# piezopiano.net
KiCad netlist of a schematic drawn in EAGLE
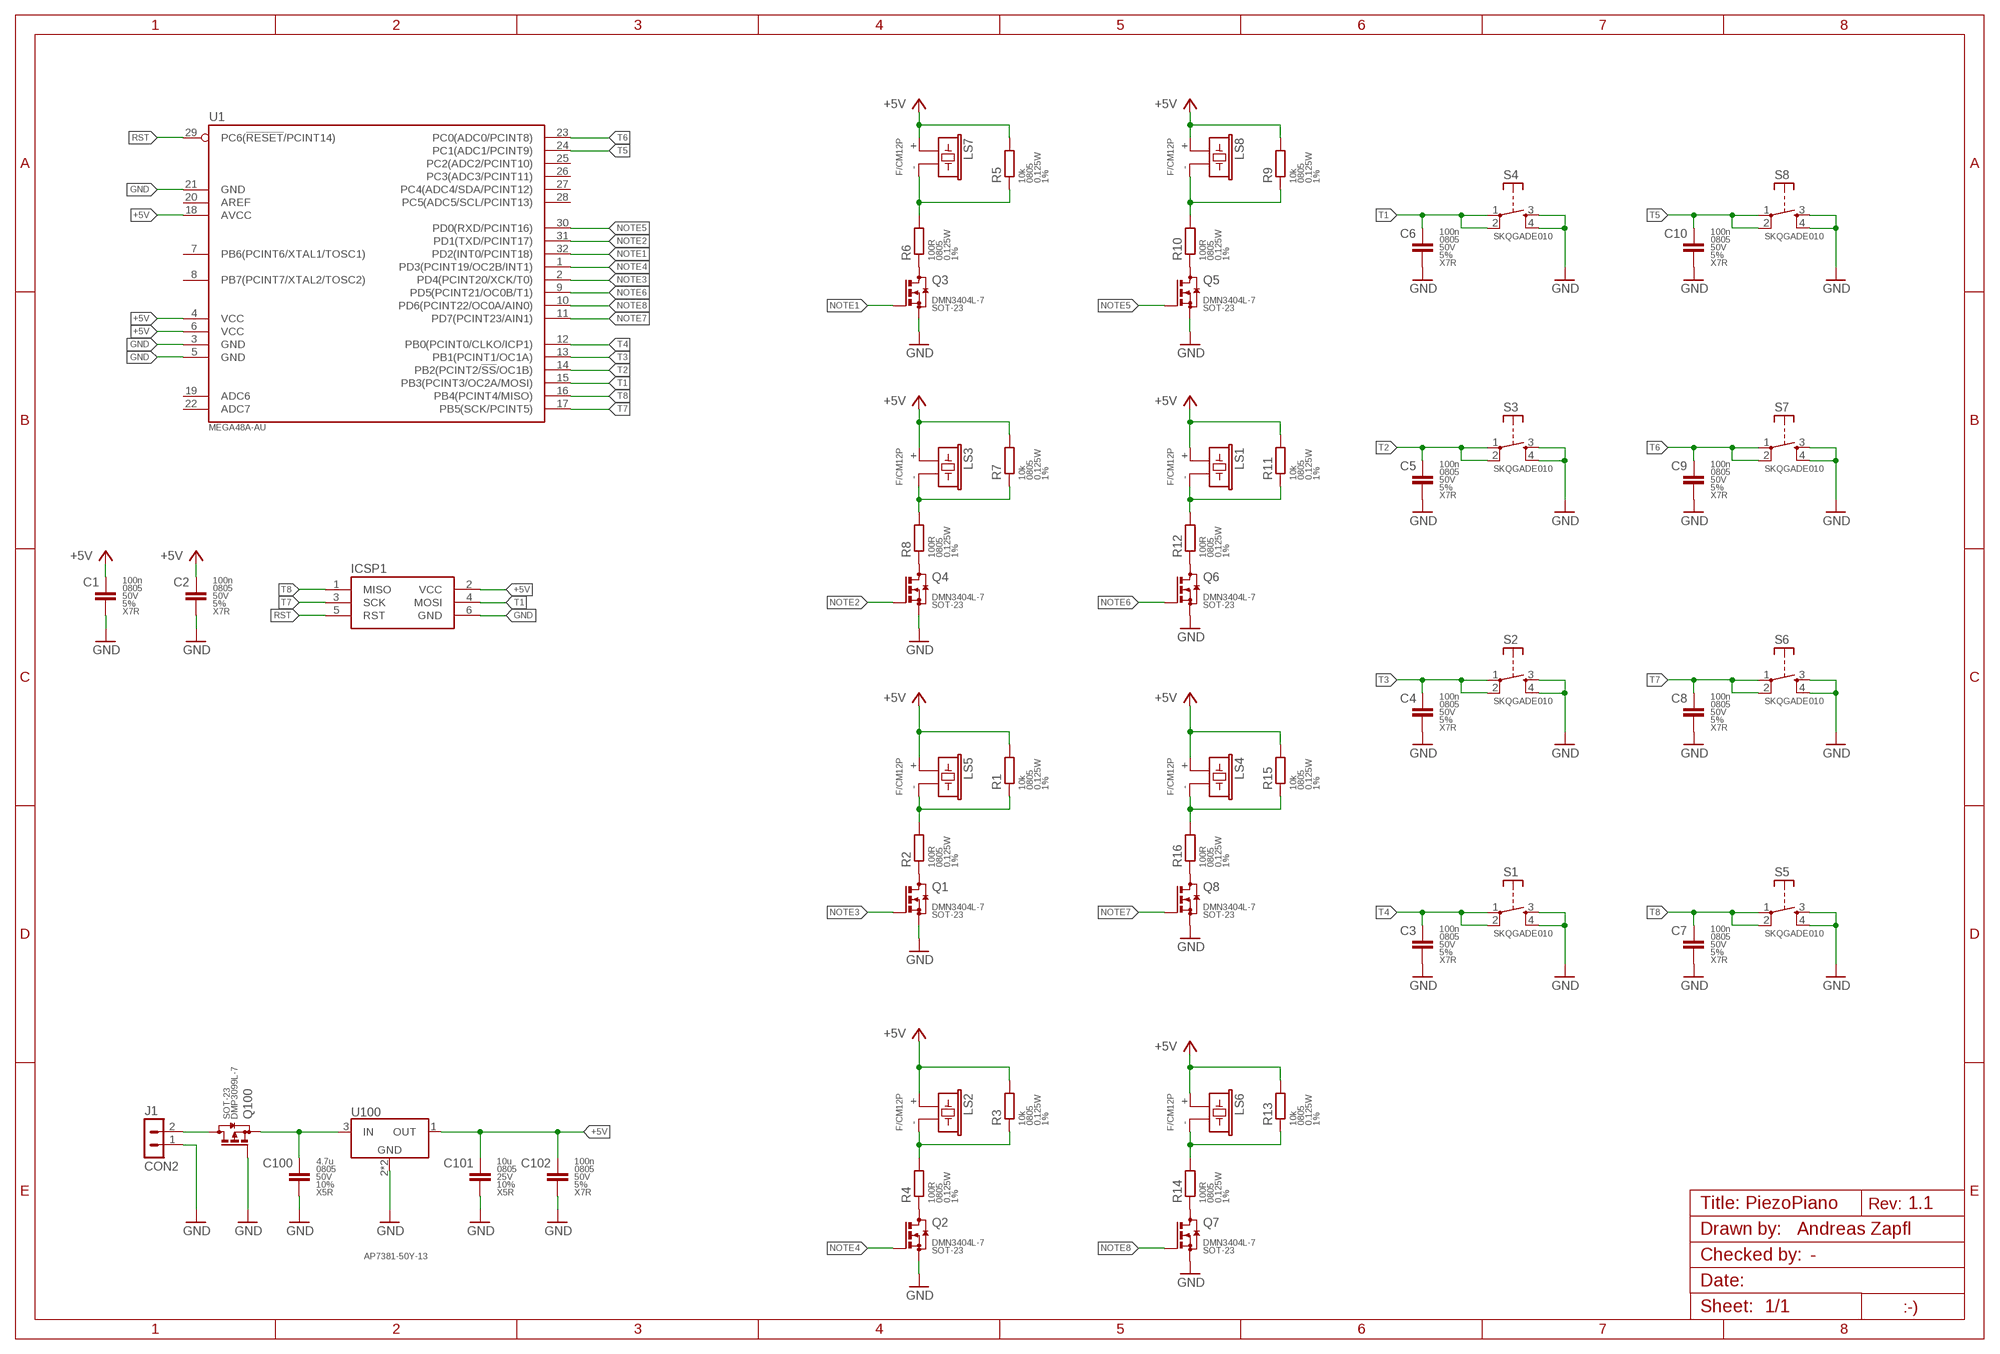
[diagram p0: schematic, sheet 1]

(export (version "E")
  (design (tool "Eeschema 10.0.6"))
  (components
    (comp (ref "C1")
      (value "100n")
      (footprint "eagle-import:C0805")
      (fields
        (field (name "PACKAGE-IN") "0805")
        (field (name "VOLTAGE") "50V")
        (field (name "TOLERANCE") "5%")
        (field (name "DIELECTRIC") "X7R")
        (field (name "MF") "Yageo")
        (field (name "MPN") "CC0805JRX7R9BB104")
      )
      (libsource (lib "eagle-import") (part "100NF-0805-50V-5%"))
    )
    (comp (ref "C2")
      (value "100n")
      (footprint "eagle-import:C0805")
      (fields
        (field (name "PACKAGE-IN") "0805")
        (field (name "VOLTAGE") "50V")
        (field (name "TOLERANCE") "5%")
        (field (name "DIELECTRIC") "X7R")
        (field (name "MF") "Yageo")
        (field (name "MPN") "CC0805JRX7R9BB104")
      )
      (libsource (lib "eagle-import") (part "100NF-0805-50V-5%"))
    )
    (comp (ref "C3")
      (value "100n")
      (footprint "eagle-import:C0805")
      (fields
        (field (name "PACKAGE-IN") "0805")
        (field (name "VOLTAGE") "50V")
        (field (name "TOLERANCE") "5%")
        (field (name "DIELECTRIC") "X7R")
        (field (name "MF") "Yageo")
        (field (name "MPN") "CC0805JRX7R9BB104")
      )
      (libsource (lib "eagle-import") (part "100NF-0805-50V-5%"))
    )
    (comp (ref "C4")
      (value "100n")
      (footprint "eagle-import:C0805")
      (fields
        (field (name "PACKAGE-IN") "0805")
        (field (name "VOLTAGE") "50V")
        (field (name "TOLERANCE") "5%")
        (field (name "DIELECTRIC") "X7R")
        (field (name "MF") "Yageo")
        (field (name "MPN") "CC0805JRX7R9BB104")
      )
      (libsource (lib "eagle-import") (part "100NF-0805-50V-5%"))
    )
    (comp (ref "C5")
      (value "100n")
      (footprint "eagle-import:C0805")
      (fields
        (field (name "PACKAGE-IN") "0805")
        (field (name "VOLTAGE") "50V")
        (field (name "TOLERANCE") "5%")
        (field (name "DIELECTRIC") "X7R")
        (field (name "MF") "Yageo")
        (field (name "MPN") "CC0805JRX7R9BB104")
      )
      (libsource (lib "eagle-import") (part "100NF-0805-50V-5%"))
    )
    (comp (ref "C6")
      (value "100n")
      (footprint "eagle-import:C0805")
      (fields
        (field (name "PACKAGE-IN") "0805")
        (field (name "VOLTAGE") "50V")
        (field (name "TOLERANCE") "5%")
        (field (name "DIELECTRIC") "X7R")
        (field (name "MF") "Yageo")
        (field (name "MPN") "CC0805JRX7R9BB104")
      )
      (libsource (lib "eagle-import") (part "100NF-0805-50V-5%"))
    )
    (comp (ref "C7")
      (value "100n")
      (footprint "eagle-import:C0805")
      (fields
        (field (name "PACKAGE-IN") "0805")
        (field (name "VOLTAGE") "50V")
        (field (name "TOLERANCE") "5%")
        (field (name "DIELECTRIC") "X7R")
        (field (name "MF") "Yageo")
        (field (name "MPN") "CC0805JRX7R9BB104")
      )
      (libsource (lib "eagle-import") (part "100NF-0805-50V-5%"))
    )
    (comp (ref "C8")
      (value "100n")
      (footprint "eagle-import:C0805")
      (fields
        (field (name "PACKAGE-IN") "0805")
        (field (name "VOLTAGE") "50V")
        (field (name "TOLERANCE") "5%")
        (field (name "DIELECTRIC") "X7R")
        (field (name "MF") "Yageo")
        (field (name "MPN") "CC0805JRX7R9BB104")
      )
      (libsource (lib "eagle-import") (part "100NF-0805-50V-5%"))
    )
    (comp (ref "C9")
      (value "100n")
      (footprint "eagle-import:C0805")
      (fields
        (field (name "PACKAGE-IN") "0805")
        (field (name "VOLTAGE") "50V")
        (field (name "TOLERANCE") "5%")
        (field (name "DIELECTRIC") "X7R")
        (field (name "MF") "Yageo")
        (field (name "MPN") "CC0805JRX7R9BB104")
      )
      (libsource (lib "eagle-import") (part "100NF-0805-50V-5%"))
    )
    (comp (ref "C10")
      (value "100n")
      (footprint "eagle-import:C0805")
      (fields
        (field (name "PACKAGE-IN") "0805")
        (field (name "VOLTAGE") "50V")
        (field (name "TOLERANCE") "5%")
        (field (name "DIELECTRIC") "X7R")
        (field (name "MF") "Yageo")
        (field (name "MPN") "CC0805JRX7R9BB104")
      )
      (libsource (lib "eagle-import") (part "100NF-0805-50V-5%"))
    )
    (comp (ref "C100")
      (value "4.7u")
      (footprint "eagle-import:C0805")
      (fields
        (field (name "PACKAGE-IN") "0805")
        (field (name "VOLTAGE") "50V")
        (field (name "TOLERANCE") "10%")
        (field (name "DIELECTRIC") "X5R")
        (field (name "MF") "Murata")
        (field (name "MPN") "GRM21BR61H475KE51L")
      )
      (libsource (lib "eagle-import") (part "4.7UF-0805-50V-10%"))
    )
    (comp (ref "C101")
      (value "10u")
      (footprint "eagle-import:C0805")
      (fields
        (field (name "PACKAGE-IN") "0805")
        (field (name "VOLTAGE") "25V")
        (field (name "TOLERANCE") "10%")
        (field (name "DIELECTRIC") "X5R")
        (field (name "MF") "Murata")
        (field (name "MPN") "GRJ21BR61E106KE01K")
      )
      (libsource (lib "eagle-import") (part "10UF-0805-25V-10%"))
    )
    (comp (ref "C102")
      (value "100n")
      (footprint "eagle-import:C0805")
      (fields
        (field (name "PACKAGE-IN") "0805")
        (field (name "VOLTAGE") "50V")
        (field (name "TOLERANCE") "5%")
        (field (name "DIELECTRIC") "X7R")
        (field (name "MF") "Yageo")
        (field (name "MPN") "CC0805JRX7R9BB104")
      )
      (libsource (lib "eagle-import") (part "100NF-0805-50V-5%"))
    )
    (comp (ref "ICSP1")
      (value "AVRISP2.54MM")
      (footprint "eagle-import:AVRISP-2.54")
      (libsource (lib "eagle-import") (part "AVRISP2.54MM"))
    )
    (comp (ref "J1")
      (value "CON2")
      (footprint "eagle-import:H2-2.54")
      (libsource (lib "eagle-import") (part "CON2"))
    )
    (comp (ref "LS1")
      (value "F/CM12P")
      (footprint "eagle-import:CM12P_5.0P")
      (fields (field (name "MF") "ZLFY") (field (name "MPN") "ZL-YDW1207-4005PA-5.0"))
      (libsource (lib "eagle-import") (part "F/CM12P"))
    )
    (comp (ref "LS2")
      (value "F/CM12P")
      (footprint "eagle-import:CM12P_5.0P")
      (fields (field (name "MF") "ZLFY") (field (name "MPN") "ZL-YDW1207-4005PA-5.0"))
      (libsource (lib "eagle-import") (part "F/CM12P"))
    )
    (comp (ref "LS3")
      (value "F/CM12P")
      (footprint "eagle-import:CM12P_5.0P")
      (fields (field (name "MF") "ZLFY") (field (name "MPN") "ZL-YDW1207-4005PA-5.0"))
      (libsource (lib "eagle-import") (part "F/CM12P"))
    )
    (comp (ref "LS4")
      (value "F/CM12P")
      (footprint "eagle-import:CM12P_5.0P")
      (fields (field (name "MF") "ZLFY") (field (name "MPN") "ZL-YDW1207-4005PA-5.0"))
      (libsource (lib "eagle-import") (part "F/CM12P"))
    )
    (comp (ref "LS5")
      (value "F/CM12P")
      (footprint "eagle-import:CM12P_5.0P")
      (fields (field (name "MF") "ZLFY") (field (name "MPN") "ZL-YDW1207-4005PA-5.0"))
      (libsource (lib "eagle-import") (part "F/CM12P"))
    )
    (comp (ref "LS6")
      (value "F/CM12P")
      (footprint "eagle-import:CM12P_5.0P")
      (fields (field (name "MF") "ZLFY") (field (name "MPN") "ZL-YDW1207-4005PA-5.0"))
      (libsource (lib "eagle-import") (part "F/CM12P"))
    )
    (comp (ref "LS7")
      (value "F/CM12P")
      (footprint "eagle-import:CM12P_5.0P")
      (fields (field (name "MF") "ZLFY") (field (name "MPN") "ZL-YDW1207-4005PA-5.0"))
      (libsource (lib "eagle-import") (part "F/CM12P"))
    )
    (comp (ref "LS8")
      (value "F/CM12P")
      (footprint "eagle-import:CM12P_5.0P")
      (fields (field (name "MF") "ZLFY") (field (name "MPN") "ZL-YDW1207-4005PA-5.0"))
      (libsource (lib "eagle-import") (part "F/CM12P"))
    )
    (comp (ref "Q1")
      (value "DMN3404L")
      (footprint "eagle-import:SOT23")
      (fields
        (field (name "MPN") "DMN3404L-7")
        (field (name "PACKAGE") "SOT-23")
        (field (name "MF") "Diodes Incorporated")
      )
      (libsource (lib "eagle-import") (part "DMN3404L"))
    )
    (comp (ref "Q2")
      (value "DMN3404L")
      (footprint "eagle-import:SOT23")
      (fields
        (field (name "MPN") "DMN3404L-7")
        (field (name "PACKAGE") "SOT-23")
        (field (name "MF") "Diodes Incorporated")
      )
      (libsource (lib "eagle-import") (part "DMN3404L"))
    )
    (comp (ref "Q3")
      (value "DMN3404L")
      (footprint "eagle-import:SOT23")
      (fields
        (field (name "MPN") "DMN3404L-7")
        (field (name "PACKAGE") "SOT-23")
        (field (name "MF") "Diodes Incorporated")
      )
      (libsource (lib "eagle-import") (part "DMN3404L"))
    )
    (comp (ref "Q4")
      (value "DMN3404L")
      (footprint "eagle-import:SOT23")
      (fields
        (field (name "MPN") "DMN3404L-7")
        (field (name "PACKAGE") "SOT-23")
        (field (name "MF") "Diodes Incorporated")
      )
      (libsource (lib "eagle-import") (part "DMN3404L"))
    )
    (comp (ref "Q5")
      (value "DMN3404L")
      (footprint "eagle-import:SOT23")
      (fields
        (field (name "MPN") "DMN3404L-7")
        (field (name "PACKAGE") "SOT-23")
        (field (name "MF") "Diodes Incorporated")
      )
      (libsource (lib "eagle-import") (part "DMN3404L"))
    )
    (comp (ref "Q6")
      (value "DMN3404L")
      (footprint "eagle-import:SOT23")
      (fields
        (field (name "MPN") "DMN3404L-7")
        (field (name "PACKAGE") "SOT-23")
        (field (name "MF") "Diodes Incorporated")
      )
      (libsource (lib "eagle-import") (part "DMN3404L"))
    )
    (comp (ref "Q7")
      (value "DMN3404L")
      (footprint "eagle-import:SOT23")
      (fields
        (field (name "MPN") "DMN3404L-7")
        (field (name "PACKAGE") "SOT-23")
        (field (name "MF") "Diodes Incorporated")
      )
      (libsource (lib "eagle-import") (part "DMN3404L"))
    )
    (comp (ref "Q8")
      (value "DMN3404L")
      (footprint "eagle-import:SOT23")
      (fields
        (field (name "MPN") "DMN3404L-7")
        (field (name "PACKAGE") "SOT-23")
        (field (name "MF") "Diodes Incorporated")
      )
      (libsource (lib "eagle-import") (part "DMN3404L"))
    )
    (comp (ref "Q100")
      (value "DMP3099L")
      (footprint "eagle-import:SOT23")
      (fields
        (field (name "MPN") "DMP3099L-7")
        (field (name "PACKAGE") "SOT-23")
        (field (name "MF") "Diodes Incorporated")
      )
      (libsource (lib "eagle-import") (part "DMP3099L"))
    )
    (comp (ref "R1")
      (value "10k")
      (footprint "eagle-import:R0805")
      (fields
        (field (name "PACKAGE-IN") "0805")
        (field (name "POWER") "0.125W")
        (field (name "TOLERANCE") "1%")
        (field (name "MF") "Yageo")
        (field (name "MPN") "RC0805FR-0710KL")
        (field (name "VOLTAGE") "150V")
      )
      (libsource (lib "eagle-import") (part "10KOHM-0805-1/8W-1%"))
    )
    (comp (ref "R2")
      (value "100R")
      (footprint "eagle-import:R0805")
      (fields
        (field (name "PACKAGE-IN") "0805")
        (field (name "POWER") "0.125W")
        (field (name "TOLERANCE") "1%")
        (field (name "MF") "Yageo")
        (field (name "MPN") "RC0805FR-07100RL")
        (field (name "VOLTAGE") "150V")
      )
      (libsource (lib "eagle-import") (part "100OHM-0805-1/8W-1%"))
    )
    (comp (ref "R3")
      (value "10k")
      (footprint "eagle-import:R0805")
      (fields
        (field (name "PACKAGE-IN") "0805")
        (field (name "POWER") "0.125W")
        (field (name "TOLERANCE") "1%")
        (field (name "MF") "Yageo")
        (field (name "MPN") "RC0805FR-0710KL")
        (field (name "VOLTAGE") "150V")
      )
      (libsource (lib "eagle-import") (part "10KOHM-0805-1/8W-1%"))
    )
    (comp (ref "R4")
      (value "100R")
      (footprint "eagle-import:R0805")
      (fields
        (field (name "PACKAGE-IN") "0805")
        (field (name "POWER") "0.125W")
        (field (name "TOLERANCE") "1%")
        (field (name "MF") "Yageo")
        (field (name "MPN") "RC0805FR-07100RL")
        (field (name "VOLTAGE") "150V")
      )
      (libsource (lib "eagle-import") (part "100OHM-0805-1/8W-1%"))
    )
    (comp (ref "R5")
      (value "10k")
      (footprint "eagle-import:R0805")
      (fields
        (field (name "PACKAGE-IN") "0805")
        (field (name "POWER") "0.125W")
        (field (name "TOLERANCE") "1%")
        (field (name "MF") "Yageo")
        (field (name "MPN") "RC0805FR-0710KL")
        (field (name "VOLTAGE") "150V")
      )
      (libsource (lib "eagle-import") (part "10KOHM-0805-1/8W-1%"))
    )
    (comp (ref "R6")
      (value "100R")
      (footprint "eagle-import:R0805")
      (fields
        (field (name "PACKAGE-IN") "0805")
        (field (name "POWER") "0.125W")
        (field (name "TOLERANCE") "1%")
        (field (name "MF") "Yageo")
        (field (name "MPN") "RC0805FR-07100RL")
        (field (name "VOLTAGE") "150V")
      )
      (libsource (lib "eagle-import") (part "100OHM-0805-1/8W-1%"))
    )
    (comp (ref "R7")
      (value "10k")
      (footprint "eagle-import:R0805")
      (fields
        (field (name "PACKAGE-IN") "0805")
        (field (name "POWER") "0.125W")
        (field (name "TOLERANCE") "1%")
        (field (name "MF") "Yageo")
        (field (name "MPN") "RC0805FR-0710KL")
        (field (name "VOLTAGE") "150V")
      )
      (libsource (lib "eagle-import") (part "10KOHM-0805-1/8W-1%"))
    )
    (comp (ref "R8")
      (value "100R")
      (footprint "eagle-import:R0805")
      (fields
        (field (name "PACKAGE-IN") "0805")
        (field (name "POWER") "0.125W")
        (field (name "TOLERANCE") "1%")
        (field (name "MF") "Yageo")
        (field (name "MPN") "RC0805FR-07100RL")
        (field (name "VOLTAGE") "150V")
      )
      (libsource (lib "eagle-import") (part "100OHM-0805-1/8W-1%"))
    )
    (comp (ref "R9")
      (value "10k")
      (footprint "eagle-import:R0805")
      (fields
        (field (name "PACKAGE-IN") "0805")
        (field (name "POWER") "0.125W")
        (field (name "TOLERANCE") "1%")
        (field (name "MF") "Yageo")
        (field (name "MPN") "RC0805FR-0710KL")
        (field (name "VOLTAGE") "150V")
      )
      (libsource (lib "eagle-import") (part "10KOHM-0805-1/8W-1%"))
    )
    (comp (ref "R10")
      (value "100R")
      (footprint "eagle-import:R0805")
      (fields
        (field (name "PACKAGE-IN") "0805")
        (field (name "POWER") "0.125W")
        (field (name "TOLERANCE") "1%")
        (field (name "MF") "Yageo")
        (field (name "MPN") "RC0805FR-07100RL")
        (field (name "VOLTAGE") "150V")
      )
      (libsource (lib "eagle-import") (part "100OHM-0805-1/8W-1%"))
    )
    (comp (ref "R11")
      (value "10k")
      (footprint "eagle-import:R0805")
      (fields
        (field (name "PACKAGE-IN") "0805")
        (field (name "POWER") "0.125W")
        (field (name "TOLERANCE") "1%")
        (field (name "MF") "Yageo")
        (field (name "MPN") "RC0805FR-0710KL")
        (field (name "VOLTAGE") "150V")
      )
      (libsource (lib "eagle-import") (part "10KOHM-0805-1/8W-1%"))
    )
    (comp (ref "R12")
      (value "100R")
      (footprint "eagle-import:R0805")
      (fields
        (field (name "PACKAGE-IN") "0805")
        (field (name "POWER") "0.125W")
        (field (name "TOLERANCE") "1%")
        (field (name "MF") "Yageo")
        (field (name "MPN") "RC0805FR-07100RL")
        (field (name "VOLTAGE") "150V")
      )
      (libsource (lib "eagle-import") (part "100OHM-0805-1/8W-1%"))
    )
    (comp (ref "R13")
      (value "10k")
      (footprint "eagle-import:R0805")
      (fields
        (field (name "PACKAGE-IN") "0805")
        (field (name "POWER") "0.125W")
        (field (name "TOLERANCE") "1%")
        (field (name "MF") "Yageo")
        (field (name "MPN") "RC0805FR-0710KL")
        (field (name "VOLTAGE") "150V")
      )
      (libsource (lib "eagle-import") (part "10KOHM-0805-1/8W-1%"))
    )
    (comp (ref "R14")
      (value "100R")
      (footprint "eagle-import:R0805")
      (fields
        (field (name "PACKAGE-IN") "0805")
        (field (name "POWER") "0.125W")
        (field (name "TOLERANCE") "1%")
        (field (name "MF") "Yageo")
        (field (name "MPN") "RC0805FR-07100RL")
        (field (name "VOLTAGE") "150V")
      )
      (libsource (lib "eagle-import") (part "100OHM-0805-1/8W-1%"))
    )
    (comp (ref "R15")
      (value "10k")
      (footprint "eagle-import:R0805")
      (fields
        (field (name "PACKAGE-IN") "0805")
        (field (name "POWER") "0.125W")
        (field (name "TOLERANCE") "1%")
        (field (name "MF") "Yageo")
        (field (name "MPN") "RC0805FR-0710KL")
        (field (name "VOLTAGE") "150V")
      )
      (libsource (lib "eagle-import") (part "10KOHM-0805-1/8W-1%"))
    )
    (comp (ref "R16")
      (value "100R")
      (footprint "eagle-import:R0805")
      (fields
        (field (name "PACKAGE-IN") "0805")
        (field (name "POWER") "0.125W")
        (field (name "TOLERANCE") "1%")
        (field (name "MF") "Yageo")
        (field (name "MPN") "RC0805FR-07100RL")
        (field (name "VOLTAGE") "150V")
      )
      (libsource (lib "eagle-import") (part "100OHM-0805-1/8W-1%"))
    )
    (comp (ref "S1")
      (value "SKQGADE010")
      (footprint "eagle-import:TACTILE_SWITCH_SMD_5.2MM")
      (libsource (lib "eagle-import") (part "SKQGADE010"))
    )
    (comp (ref "S2")
      (value "SKQGADE010")
      (footprint "eagle-import:TACTILE_SWITCH_SMD_5.2MM")
      (libsource (lib "eagle-import") (part "SKQGADE010"))
    )
    (comp (ref "S3")
      (value "SKQGADE010")
      (footprint "eagle-import:TACTILE_SWITCH_SMD_5.2MM")
      (libsource (lib "eagle-import") (part "SKQGADE010"))
    )
    (comp (ref "S4")
      (value "SKQGADE010")
      (footprint "eagle-import:TACTILE_SWITCH_SMD_5.2MM")
      (libsource (lib "eagle-import") (part "SKQGADE010"))
    )
    (comp (ref "S5")
      (value "SKQGADE010")
      (footprint "eagle-import:TACTILE_SWITCH_SMD_5.2MM")
      (libsource (lib "eagle-import") (part "SKQGADE010"))
    )
    (comp (ref "S6")
      (value "SKQGADE010")
      (footprint "eagle-import:TACTILE_SWITCH_SMD_5.2MM")
      (libsource (lib "eagle-import") (part "SKQGADE010"))
    )
    (comp (ref "S7")
      (value "SKQGADE010")
      (footprint "eagle-import:TACTILE_SWITCH_SMD_5.2MM")
      (libsource (lib "eagle-import") (part "SKQGADE010"))
    )
    (comp (ref "S8")
      (value "SKQGADE010")
      (footprint "eagle-import:TACTILE_SWITCH_SMD_5.2MM")
      (libsource (lib "eagle-import") (part "SKQGADE010"))
    )
    (comp (ref "U1")
      (value "MEGA48A-AU")
      (footprint "eagle-import:TQFP32-08")
      (fields (field (name "MF") "Atmel") (field (name "MPN") "ATmega48A-AU"))
      (libsource (lib "eagle-import") (part "MEGA48A-AU"))
    )
    (comp (ref "U100")
      (value "AP7381-50Y-13")
      (footprint "eagle-import:SOT89")
      (fields (field (name "MF") "Diodes Incorporated"))
      (libsource (lib "eagle-import") (part "AP7381-50Y-13"))
    )
  )
  (nets
    (net (code "1") (name "+5V") (class "Default")
      (node (ref "C1") (pin "1") (pinfunction "1_1") (pintype "passive"))
      (node (ref "C101") (pin "1") (pinfunction "1_1") (pintype "passive"))
      (node (ref "C102") (pin "1") (pinfunction "1_1") (pintype "passive"))
      (node (ref "C2") (pin "1") (pinfunction "1_1") (pintype "passive"))
      (node (ref "ICSP1") (pin "2") (pinfunction "VCC_2") (pintype "power_in"))
      (node (ref "LS1") (pin "+") (pinfunction "1_+") (pintype "passive"))
      (node (ref "LS2") (pin "+") (pinfunction "1_+") (pintype "passive"))
      (node (ref "LS3") (pin "+") (pinfunction "1_+") (pintype "passive"))
      (node (ref "LS4") (pin "+") (pinfunction "1_+") (pintype "passive"))
      (node (ref "LS5") (pin "+") (pinfunction "1_+") (pintype "passive"))
      (node (ref "LS6") (pin "+") (pinfunction "1_+") (pintype "passive"))
      (node (ref "LS7") (pin "+") (pinfunction "1_+") (pintype "passive"))
      (node (ref "LS8") (pin "+") (pinfunction "1_+") (pintype "passive"))
      (node (ref "R1") (pin "2") (pinfunction "2_2") (pintype "passive"))
      (node (ref "R11") (pin "2") (pinfunction "2_2") (pintype "passive"))
      (node (ref "R13") (pin "2") (pinfunction "2_2") (pintype "passive"))
      (node (ref "R15") (pin "2") (pinfunction "2_2") (pintype "passive"))
      (node (ref "R3") (pin "2") (pinfunction "2_2") (pintype "passive"))
      (node (ref "R5") (pin "2") (pinfunction "2_2") (pintype "passive"))
      (node (ref "R7") (pin "2") (pinfunction "2_2") (pintype "passive"))
      (node (ref "R9") (pin "2") (pinfunction "2_2") (pintype "passive"))
      (node (ref "U1") (pin "18") (pinfunction "AVCC_18") (pintype "power_in"))
      (node (ref "U1") (pin "4") (pinfunction "VCC_4") (pintype "power_in"))
      (node (ref "U1") (pin "6") (pinfunction "VCC_6") (pintype "power_in"))
      (node (ref "U100") (pin "1") (pinfunction "OUT_1") (pintype "output"))
    )
    (net (code "2") (name "GND") (class "Default")
      (node (ref "C1") (pin "2") (pinfunction "2_2") (pintype "passive"))
      (node (ref "C10") (pin "2") (pinfunction "2_2") (pintype "passive"))
      (node (ref "C100") (pin "2") (pinfunction "2_2") (pintype "passive"))
      (node (ref "C101") (pin "2") (pinfunction "2_2") (pintype "passive"))
      (node (ref "C102") (pin "2") (pinfunction "2_2") (pintype "passive"))
      (node (ref "C2") (pin "2") (pinfunction "2_2") (pintype "passive"))
      (node (ref "C3") (pin "2") (pinfunction "2_2") (pintype "passive"))
      (node (ref "C4") (pin "2") (pinfunction "2_2") (pintype "passive"))
      (node (ref "C5") (pin "2") (pinfunction "2_2") (pintype "passive"))
      (node (ref "C6") (pin "2") (pinfunction "2_2") (pintype "passive"))
      (node (ref "C7") (pin "2") (pinfunction "2_2") (pintype "passive"))
      (node (ref "C8") (pin "2") (pinfunction "2_2") (pintype "passive"))
      (node (ref "C9") (pin "2") (pinfunction "2_2") (pintype "passive"))
      (node (ref "ICSP1") (pin "6") (pinfunction "GND_6") (pintype "power_in"))
      (node (ref "J1") (pin "1") (pinfunction "1_1") (pintype "passive"))
      (node (ref "Q1") (pin "2") (pinfunction "S_2") (pintype "passive"))
      (node (ref "Q100") (pin "1") (pinfunction "G_1") (pintype "passive"))
      (node (ref "Q2") (pin "2") (pinfunction "S_2") (pintype "passive"))
      (node (ref "Q3") (pin "2") (pinfunction "S_2") (pintype "passive"))
      (node (ref "Q4") (pin "2") (pinfunction "S_2") (pintype "passive"))
      (node (ref "Q5") (pin "2") (pinfunction "S_2") (pintype "passive"))
      (node (ref "Q6") (pin "2") (pinfunction "S_2") (pintype "passive"))
      (node (ref "Q7") (pin "2") (pinfunction "S_2") (pintype "passive"))
      (node (ref "Q8") (pin "2") (pinfunction "S_2") (pintype "passive"))
      (node (ref "S1") (pin "3") (pinfunction "S_3") (pintype "passive"))
      (node (ref "S1") (pin "4") (pinfunction "S_4") (pintype "passive"))
      (node (ref "S2") (pin "3") (pinfunction "S_3") (pintype "passive"))
      (node (ref "S2") (pin "4") (pinfunction "S_4") (pintype "passive"))
      (node (ref "S3") (pin "3") (pinfunction "S_3") (pintype "passive"))
      (node (ref "S3") (pin "4") (pinfunction "S_4") (pintype "passive"))
      (node (ref "S4") (pin "3") (pinfunction "S_3") (pintype "passive"))
      (node (ref "S4") (pin "4") (pinfunction "S_4") (pintype "passive"))
      (node (ref "S5") (pin "3") (pinfunction "S_3") (pintype "passive"))
      (node (ref "S5") (pin "4") (pinfunction "S_4") (pintype "passive"))
      (node (ref "S6") (pin "3") (pinfunction "S_3") (pintype "passive"))
      (node (ref "S6") (pin "4") (pinfunction "S_4") (pintype "passive"))
      (node (ref "S7") (pin "3") (pinfunction "S_3") (pintype "passive"))
      (node (ref "S7") (pin "4") (pinfunction "S_4") (pintype "passive"))
      (node (ref "S8") (pin "3") (pinfunction "S_3") (pintype "passive"))
      (node (ref "S8") (pin "4") (pinfunction "S_4") (pintype "passive"))
      (node (ref "U1") (pin "21") (pinfunction "GND_21") (pintype "power_in"))
      (node (ref "U1") (pin "3") (pinfunction "GND_3") (pintype "power_in"))
      (node (ref "U1") (pin "5") (pinfunction "GND_5") (pintype "power_in"))
      (node (ref "U100") (pin "2") (pinfunction "GND_2") (pintype "power_in"))
      (node (ref "U100") (pin "2@1") (pinfunction "GND_2@1") (pintype "power_in"))
    )
    (net (code "3") (name "NOTE1") (class "Default")
      (node (ref "Q3") (pin "1") (pinfunction "G_1") (pintype "passive"))
      (node (ref "U1") (pin "32") (pinfunction "PD2(INT0/PCINT18)_32") (pintype "bidirectional"))
    )
    (net (code "4") (name "NOTE2") (class "Default")
      (node (ref "Q4") (pin "1") (pinfunction "G_1") (pintype "passive"))
      (node (ref "U1") (pin "31") (pinfunction "PD1(TXD/PCINT17)_31") (pintype "bidirectional"))
    )
    (net (code "5") (name "NOTE3") (class "Default")
      (node (ref "Q1") (pin "1") (pinfunction "G_1") (pintype "passive"))
      (node (ref "U1") (pin "2") (pinfunction "PD4(PCINT20/XCK/T0)_2") (pintype "bidirectional"))
    )
    (net (code "6") (name "NOTE4") (class "Default")
      (node (ref "Q2") (pin "1") (pinfunction "G_1") (pintype "passive"))
      (node (ref "U1") (pin "1") (pinfunction "PD3(PCINT19/OC2B/INT1)_1") (pintype "bidirectional"))
    )
    (net (code "7") (name "NOTE5") (class "Default")
      (node (ref "Q5") (pin "1") (pinfunction "G_1") (pintype "passive"))
      (node (ref "U1") (pin "30") (pinfunction "PD0(RXD/PCINT16)_30") (pintype "bidirectional"))
    )
    (net (code "8") (name "NOTE6") (class "Default")
      (node (ref "Q6") (pin "1") (pinfunction "G_1") (pintype "passive"))
      (node (ref "U1") (pin "9") (pinfunction "PD5(PCINT21/OC0B/T1)_9") (pintype "bidirectional"))
    )
    (net (code "9") (name "NOTE7") (class "Default")
      (node (ref "Q8") (pin "1") (pinfunction "G_1") (pintype "passive"))
      (node (ref "U1") (pin "11") (pinfunction "PD7(PCINT23/AIN1)_11") (pintype "bidirectional"))
    )
    (net (code "10") (name "NOTE8") (class "Default")
      (node (ref "Q7") (pin "1") (pinfunction "G_1") (pintype "passive"))
      (node (ref "U1") (pin "10") (pinfunction "PD6(PCINT22/OC0A/AIN0)_10") (pintype "bidirectional"))
    )
    (net (code "11") (name "Net-(LS1-2)") (class "Default")
      (node (ref "LS1") (pin "-") (pinfunction "2_-") (pintype "passive"))
      (node (ref "R11") (pin "1") (pinfunction "1_1") (pintype "passive"))
      (node (ref "R12") (pin "2") (pinfunction "2_2") (pintype "passive"))
    )
    (net (code "12") (name "Net-(LS2-2)") (class "Default")
      (node (ref "LS2") (pin "-") (pinfunction "2_-") (pintype "passive"))
      (node (ref "R3") (pin "1") (pinfunction "1_1") (pintype "passive"))
      (node (ref "R4") (pin "2") (pinfunction "2_2") (pintype "passive"))
    )
    (net (code "13") (name "Net-(LS3-2)") (class "Default")
      (node (ref "LS3") (pin "-") (pinfunction "2_-") (pintype "passive"))
      (node (ref "R7") (pin "1") (pinfunction "1_1") (pintype "passive"))
      (node (ref "R8") (pin "2") (pinfunction "2_2") (pintype "passive"))
    )
    (net (code "14") (name "Net-(LS4-2)") (class "Default")
      (node (ref "LS4") (pin "-") (pinfunction "2_-") (pintype "passive"))
      (node (ref "R15") (pin "1") (pinfunction "1_1") (pintype "passive"))
      (node (ref "R16") (pin "2") (pinfunction "2_2") (pintype "passive"))
    )
    (net (code "15") (name "Net-(LS5-2)") (class "Default")
      (node (ref "LS5") (pin "-") (pinfunction "2_-") (pintype "passive"))
      (node (ref "R1") (pin "1") (pinfunction "1_1") (pintype "passive"))
      (node (ref "R2") (pin "2") (pinfunction "2_2") (pintype "passive"))
    )
    (net (code "16") (name "Net-(LS6-2)") (class "Default")
      (node (ref "LS6") (pin "-") (pinfunction "2_-") (pintype "passive"))
      (node (ref "R13") (pin "1") (pinfunction "1_1") (pintype "passive"))
      (node (ref "R14") (pin "2") (pinfunction "2_2") (pintype "passive"))
    )
    (net (code "17") (name "Net-(LS7-2)") (class "Default")
      (node (ref "LS7") (pin "-") (pinfunction "2_-") (pintype "passive"))
      (node (ref "R5") (pin "1") (pinfunction "1_1") (pintype "passive"))
      (node (ref "R6") (pin "2") (pinfunction "2_2") (pintype "passive"))
    )
    (net (code "18") (name "Net-(LS8-2)") (class "Default")
      (node (ref "LS8") (pin "-") (pinfunction "2_-") (pintype "passive"))
      (node (ref "R10") (pin "2") (pinfunction "2_2") (pintype "passive"))
      (node (ref "R9") (pin "1") (pinfunction "1_1") (pintype "passive"))
    )
    (net (code "19") (name "Net-(Q1-D)") (class "Default")
      (node (ref "Q1") (pin "3") (pinfunction "D_3") (pintype "passive"))
      (node (ref "R2") (pin "1") (pinfunction "1_1") (pintype "passive"))
    )
    (net (code "20") (name "Net-(Q2-D)") (class "Default")
      (node (ref "Q2") (pin "3") (pinfunction "D_3") (pintype "passive"))
      (node (ref "R4") (pin "1") (pinfunction "1_1") (pintype "passive"))
    )
    (net (code "21") (name "Net-(Q3-D)") (class "Default")
      (node (ref "Q3") (pin "3") (pinfunction "D_3") (pintype "passive"))
      (node (ref "R6") (pin "1") (pinfunction "1_1") (pintype "passive"))
    )
    (net (code "22") (name "Net-(Q4-D)") (class "Default")
      (node (ref "Q4") (pin "3") (pinfunction "D_3") (pintype "passive"))
      (node (ref "R8") (pin "1") (pinfunction "1_1") (pintype "passive"))
    )
    (net (code "23") (name "Net-(Q5-D)") (class "Default")
      (node (ref "Q5") (pin "3") (pinfunction "D_3") (pintype "passive"))
      (node (ref "R10") (pin "1") (pinfunction "1_1") (pintype "passive"))
    )
    (net (code "24") (name "Net-(Q6-D)") (class "Default")
      (node (ref "Q6") (pin "3") (pinfunction "D_3") (pintype "passive"))
      (node (ref "R12") (pin "1") (pinfunction "1_1") (pintype "passive"))
    )
    (net (code "25") (name "Net-(Q7-D)") (class "Default")
      (node (ref "Q7") (pin "3") (pinfunction "D_3") (pintype "passive"))
      (node (ref "R14") (pin "1") (pinfunction "1_1") (pintype "passive"))
    )
    (net (code "26") (name "Net-(Q8-D)") (class "Default")
      (node (ref "Q8") (pin "3") (pinfunction "D_3") (pintype "passive"))
      (node (ref "R16") (pin "1") (pinfunction "1_1") (pintype "passive"))
    )
    (net (code "27") (name "Net-(Q100-D)") (class "Default")
      (node (ref "J1") (pin "2") (pinfunction "2_2") (pintype "passive"))
      (node (ref "Q100") (pin "3") (pinfunction "D_3") (pintype "passive"))
    )
    (net (code "28") (name "Net-(Q100-S)") (class "Default")
      (node (ref "C100") (pin "1") (pinfunction "1_1") (pintype "passive"))
      (node (ref "Q100") (pin "2") (pinfunction "S_2") (pintype "passive"))
      (node (ref "U100") (pin "3") (pinfunction "IN_3") (pintype "input"))
    )
    (net (code "29") (name "RST") (class "Default")
      (node (ref "ICSP1") (pin "5") (pinfunction "RST_5") (pintype "output"))
      (node (ref "U1") (pin "29") (pinfunction "PC6(~{RESET}/PCINT14)_29") (pintype "bidirectional"))
    )
    (net (code "30") (name "T1") (class "Default")
      (node (ref "C6") (pin "1") (pinfunction "1_1") (pintype "passive"))
      (node (ref "ICSP1") (pin "4") (pinfunction "MOSI_4") (pintype "output"))
      (node (ref "S4") (pin "1") (pinfunction "P_1") (pintype "passive"))
      (node (ref "S4") (pin "2") (pinfunction "P_2") (pintype "passive"))
      (node (ref "U1") (pin "15") (pinfunction "PB3(PCINT3/OC2A/MOSI)_15") (pintype "bidirectional"))
    )
    (net (code "31") (name "T2") (class "Default")
      (node (ref "C5") (pin "1") (pinfunction "1_1") (pintype "passive"))
      (node (ref "S3") (pin "1") (pinfunction "P_1") (pintype "passive"))
      (node (ref "S3") (pin "2") (pinfunction "P_2") (pintype "passive"))
      (node (ref "U1") (pin "14") (pinfunction "PB2(PCINT2/~{SS}/OC1B)_14") (pintype "bidirectional"))
    )
    (net (code "32") (name "T3") (class "Default")
      (node (ref "C4") (pin "1") (pinfunction "1_1") (pintype "passive"))
      (node (ref "S2") (pin "1") (pinfunction "P_1") (pintype "passive"))
      (node (ref "S2") (pin "2") (pinfunction "P_2") (pintype "passive"))
      (node (ref "U1") (pin "13") (pinfunction "PB1(PCINT1/OC1A)_13") (pintype "bidirectional"))
    )
    (net (code "33") (name "T4") (class "Default")
      (node (ref "C3") (pin "1") (pinfunction "1_1") (pintype "passive"))
      (node (ref "S1") (pin "1") (pinfunction "P_1") (pintype "passive"))
      (node (ref "S1") (pin "2") (pinfunction "P_2") (pintype "passive"))
      (node (ref "U1") (pin "12") (pinfunction "PB0(PCINT0/CLKO/ICP1)_12") (pintype "bidirectional"))
    )
    (net (code "34") (name "T5") (class "Default")
      (node (ref "C10") (pin "1") (pinfunction "1_1") (pintype "passive"))
      (node (ref "S8") (pin "1") (pinfunction "P_1") (pintype "passive"))
      (node (ref "S8") (pin "2") (pinfunction "P_2") (pintype "passive"))
      (node (ref "U1") (pin "24") (pinfunction "PC1(ADC1/PCINT9)_24") (pintype "bidirectional"))
    )
    (net (code "35") (name "T6") (class "Default")
      (node (ref "C9") (pin "1") (pinfunction "1_1") (pintype "passive"))
      (node (ref "S7") (pin "1") (pinfunction "P_1") (pintype "passive"))
      (node (ref "S7") (pin "2") (pinfunction "P_2") (pintype "passive"))
      (node (ref "U1") (pin "23") (pinfunction "PC0(ADC0/PCINT8)_23") (pintype "bidirectional"))
    )
    (net (code "36") (name "T7") (class "Default")
      (node (ref "C8") (pin "1") (pinfunction "1_1") (pintype "passive"))
      (node (ref "ICSP1") (pin "3") (pinfunction "SCK_3") (pintype "output"))
      (node (ref "S6") (pin "1") (pinfunction "P_1") (pintype "passive"))
      (node (ref "S6") (pin "2") (pinfunction "P_2") (pintype "passive"))
      (node (ref "U1") (pin "17") (pinfunction "PB5(SCK/PCINT5)_17") (pintype "bidirectional"))
    )
    (net (code "37") (name "T8") (class "Default")
      (node (ref "C7") (pin "1") (pinfunction "1_1") (pintype "passive"))
      (node (ref "ICSP1") (pin "1") (pinfunction "MISO_1") (pintype "input"))
      (node (ref "S5") (pin "1") (pinfunction "P_1") (pintype "passive"))
      (node (ref "S5") (pin "2") (pinfunction "P_2") (pintype "passive"))
      (node (ref "U1") (pin "16") (pinfunction "PB4(PCINT4/MISO)_16") (pintype "bidirectional"))
    )
    (net (code "38") (name "unconnected-(U1-ADC6-Pad19)") (class "Default")
      (node (ref "U1") (pin "19") (pinfunction "ADC6_19") (pintype "bidirectional"))
    )
    (net (code "39") (name "unconnected-(U1-ADC7-Pad22)") (class "Default")
      (node (ref "U1") (pin "22") (pinfunction "ADC7_22") (pintype "bidirectional"))
    )
    (net (code "40") (name "unconnected-(U1-AREF-Pad20)") (class "Default")
      (node (ref "U1") (pin "20") (pinfunction "AREF_20") (pintype "passive"))
    )
    (net (code "41") (name "unconnected-(U1-PB6(PCINT6{slash}XTAL1{slash}TOSC1)-Pad7)") (class "Default")
      (node (ref "U1") (pin "7") (pinfunction "PB6(PCINT6/XTAL1/TOSC1)_7") (pintype "bidirectional"))
    )
    (net (code "42") (name "unconnected-(U1-PB7(PCINT7{slash}XTAL2{slash}TOSC2)-Pad8)") (class "Default")
      (node (ref "U1") (pin "8") (pinfunction "PB7(PCINT7/XTAL2/TOSC2)_8") (pintype "bidirectional"))
    )
    (net (code "43") (name "unconnected-(U1-PC2(ADC2{slash}PCINT10)-Pad25)") (class "Default")
      (node (ref "U1") (pin "25") (pinfunction "PC2(ADC2/PCINT10)_25") (pintype "bidirectional"))
    )
    (net (code "44") (name "unconnected-(U1-PC3(ADC3{slash}PCINT11)-Pad26)") (class "Default")
      (node (ref "U1") (pin "26") (pinfunction "PC3(ADC3/PCINT11)_26") (pintype "bidirectional"))
    )
    (net (code "45") (name "unconnected-(U1-PC4(ADC4{slash}SDA{slash}PCINT12)-Pad27)") (class "Default")
      (node (ref "U1") (pin "27") (pinfunction "PC4(ADC4/SDA/PCINT12)_27") (pintype "bidirectional"))
    )
    (net (code "46") (name "unconnected-(U1-PC5(ADC5{slash}SCL{slash}PCINT13)-Pad28)") (class "Default")
      (node (ref "U1") (pin "28") (pinfunction "PC5(ADC5/SCL/PCINT13)_28") (pintype "bidirectional"))
    )
  )
)
